# Experiment_1_0_0_0.net
KiCad netlist of a schematic drawn in Altium Designer
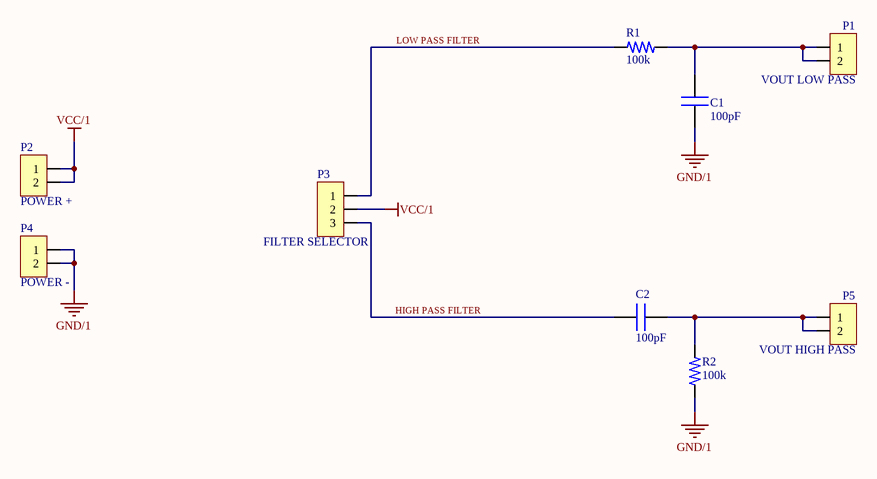
[diagram p0: Experiment 1 0.0.0.SchDoc]

(export (version "E")
  (design (tool "Eeschema 10.0.6"))
  (components
    (comp (ref "C1")
      (value "100pF")
      (footprint "CAP-H5")
      (description "CAP CER 100PF 50V X7R RADIAL")
      (fields
        (field (name "MANUFACTURER") "Vishay BC Components")
        (field (name "MANUFACTURER PART NUMBER") "K101K10X7RF5UH5")
      )
      (libsource (lib "Capacitors") (part "K101K10X7RF5UH5"))
    )
    (comp (ref "C2")
      (value "100pF")
      (footprint "CAP-H5")
      (description "CAP CER 100PF 50V X7R RADIAL")
      (fields
        (field (name "MANUFACTURER") "Vishay BC Components")
        (field (name "MANUFACTURER PART NUMBER") "K101K10X7RF5UH5")
      )
      (libsource (lib "Capacitors") (part "K101K10X7RF5UH5"))
    )
    (comp (ref "P1")
      (value "VOUT LOW PASS")
      (footprint "PINHD-1X02 ONCE")
      (description "CONN HEADER 2POS .100\" STR TIN")
      (fields
        (field (name "MANUFACTURER") "Molex, LLC")
        (field (name "MANUFACTURER PART NUMBER") "0901200122")
      )
      (libsource (lib "Connectors") (part "PIN HEADER 1X02 ONCE"))
    )
    (comp (ref "P2")
      (value "POWER +")
      (footprint "PINHD-1X02 ONCE")
      (description "CONN HEADER 2POS .100\" STR TIN")
      (fields
        (field (name "MANUFACTURER") "Molex, LLC")
        (field (name "MANUFACTURER PART NUMBER") "0901200122")
      )
      (libsource (lib "") (part "PIN HEADER 1X02 ONCE_1"))
    )
    (comp (ref "P3")
      (value "FILTER SELECTOR")
      (footprint "PINHD-1X03")
      (description "CONN HEADER 3POS .100\" STR TIN")
      (fields
        (field (name "MANUFACTURER") "Molex, LLC")
        (field (name "MANUFACTURER PART NUMBER") "0901200123")
      )
      (libsource (lib "Connectors") (part "PIN HEADER 1X03"))
    )
    (comp (ref "P4")
      (value "POWER -")
      (footprint "PINHD-1X02 ONCE")
      (description "CONN HEADER 2POS .100\" STR TIN")
      (fields
        (field (name "MANUFACTURER") "Molex, LLC")
        (field (name "MANUFACTURER PART NUMBER") "0901200122")
      )
      (libsource (lib "") (part "PIN HEADER 1X02 ONCE_1"))
    )
    (comp (ref "P5")
      (value "VOUT HIGH PASS")
      (footprint "PINHD-1X02 ONCE")
      (description "CONN HEADER 2POS .100\" STR TIN")
      (fields
        (field (name "MANUFACTURER") "Molex, LLC")
        (field (name "MANUFACTURER PART NUMBER") "0901200122")
      )
      (libsource (lib "Connectors") (part "PIN HEADER 1X02 ONCE"))
    )
    (comp (ref "R1")
      (value "100k")
      (footprint "R Axial 0.25")
      (description "RES 100K OHM 1/4W 5% AXIAL")
      (fields
        (field (name "MANUFACTURER") "Yageo")
        (field (name "MANUFACTURER PART NUMBER") "CFR-25JB-52-100K")
      )
      (libsource (lib "Resistors") (part "CFR-25JB-52-100K"))
    )
    (comp (ref "R2")
      (value "100k")
      (footprint "R Axial 0.25")
      (description "RES 100K OHM 1/4W 5% AXIAL")
      (fields
        (field (name "MANUFACTURER") "Yageo")
        (field (name "MANUFACTURER PART NUMBER") "CFR-25JB-52-100K")
      )
      (libsource (lib "Resistors") (part "CFR-25JB-52-100K"))
    )
  )
  (nets
    (net (code "1") (name "GND{slash}1") (class "Default")
      (node (ref "C1") (pin "2") (pinfunction "2_2") (pintype "passive"))
      (node (ref "P4") (pin "1") (pinfunction "1_1") (pintype "passive"))
      (node (ref "P4") (pin "2") (pinfunction "2_2") (pintype "passive"))
      (node (ref "R2") (pin "1") (pinfunction "1_1") (pintype "passive"))
    )
    (net (code "2") (name "Net-(C1-Pad1)") (class "Default")
      (node (ref "C1") (pin "1") (pinfunction "1_1") (pintype "passive"))
      (node (ref "P1") (pin "1") (pinfunction "1_1") (pintype "passive"))
      (node (ref "P1") (pin "2") (pinfunction "2_2") (pintype "passive"))
      (node (ref "R1") (pin "2") (pinfunction "2_2") (pintype "passive"))
    )
    (net (code "3") (name "Net-(C2-Pad1)") (class "Default")
      (node (ref "C2") (pin "1") (pinfunction "1_1") (pintype "passive"))
      (node (ref "P3") (pin "3") (pinfunction "3_3") (pintype "passive"))
    )
    (net (code "4") (name "Net-(C2-Pad2)") (class "Default")
      (node (ref "C2") (pin "2") (pinfunction "2_2") (pintype "passive"))
      (node (ref "P5") (pin "1") (pinfunction "1_1") (pintype "passive"))
      (node (ref "P5") (pin "2") (pinfunction "2_2") (pintype "passive"))
      (node (ref "R2") (pin "2") (pinfunction "2_2") (pintype "passive"))
    )
    (net (code "5") (name "Net-(P3-Pad1)") (class "Default")
      (node (ref "P3") (pin "1") (pinfunction "1_1") (pintype "passive"))
      (node (ref "R1") (pin "1") (pinfunction "1_1") (pintype "passive"))
    )
    (net (code "6") (name "VCC{slash}1") (class "Default")
      (node (ref "P2") (pin "1") (pinfunction "1_1") (pintype "passive"))
      (node (ref "P2") (pin "2") (pinfunction "2_2") (pintype "passive"))
      (node (ref "P3") (pin "2") (pinfunction "2_2") (pintype "passive"))
    )
  )
)
